# LAN_HUB_imp.net
KiCad netlist of a schematic drawn in EAGLE
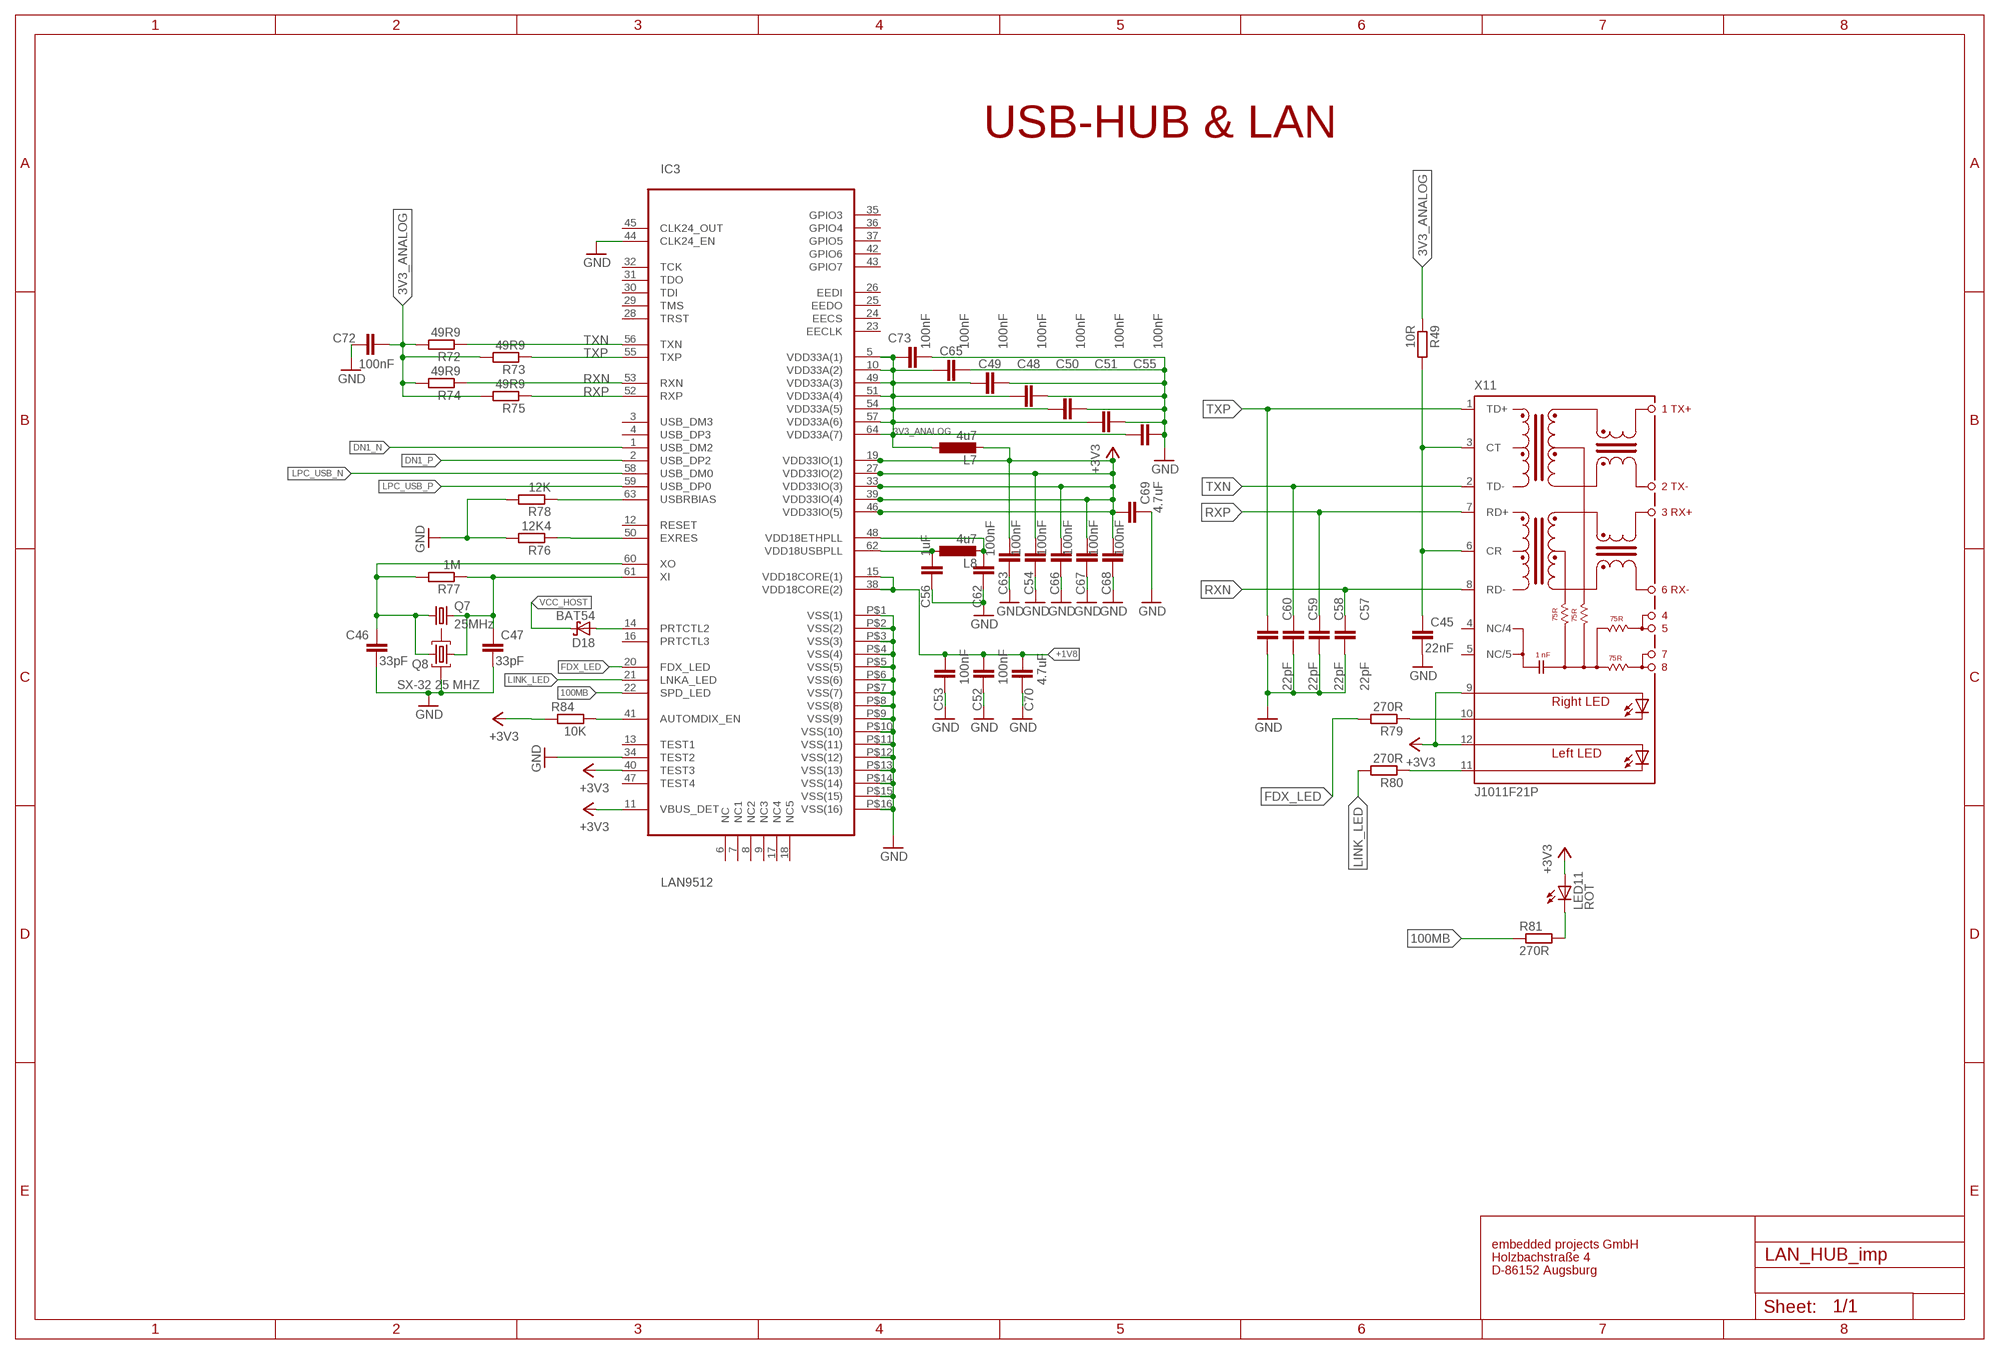
[diagram p0: schematic, sheet 1]

(export (version "E")
  (design (tool "Eeschema 10.0.6"))
  (components
    (comp (ref "C45")
      (value "22nF")
      (footprint "eagle-import:C0805")
      (libsource (lib "eagle-import") (part "C-EUC0805"))
    )
    (comp (ref "C46")
      (value "33pF")
      (footprint "eagle-import:C0805")
      (libsource (lib "eagle-import") (part "C-EUC0805"))
    )
    (comp (ref "C47")
      (value "33pF")
      (footprint "eagle-import:C0805")
      (libsource (lib "eagle-import") (part "C-EUC0805"))
    )
    (comp (ref "C48")
      (value "100nF")
      (footprint "eagle-import:C0805")
      (libsource (lib "eagle-import") (part "C-EUC0805"))
    )
    (comp (ref "C49")
      (value "100nF")
      (footprint "eagle-import:C0805")
      (libsource (lib "eagle-import") (part "C-EUC0805"))
    )
    (comp (ref "C50")
      (value "100nF")
      (footprint "eagle-import:C0805")
      (libsource (lib "eagle-import") (part "C-EUC0805"))
    )
    (comp (ref "C51")
      (value "100nF")
      (footprint "eagle-import:C0805")
      (libsource (lib "eagle-import") (part "C-EUC0805"))
    )
    (comp (ref "C52")
      (value "100nF")
      (footprint "eagle-import:C0805")
      (libsource (lib "eagle-import") (part "C-EUC0805"))
    )
    (comp (ref "C53")
      (value "100nF")
      (footprint "eagle-import:C0805")
      (libsource (lib "eagle-import") (part "C-EUC0805"))
    )
    (comp (ref "C54")
      (value "100nF")
      (footprint "eagle-import:C0805")
      (libsource (lib "eagle-import") (part "C-EUC0805"))
    )
    (comp (ref "C55")
      (value "100nF")
      (footprint "eagle-import:C0805")
      (libsource (lib "eagle-import") (part "C-EUC0805"))
    )
    (comp (ref "C56")
      (value "1uF")
      (footprint "eagle-import:C0805")
      (libsource (lib "eagle-import") (part "C-EUC0805"))
    )
    (comp (ref "C57")
      (value "22pF")
      (footprint "eagle-import:C0805")
      (libsource (lib "eagle-import") (part "C-EUC0805"))
    )
    (comp (ref "C58")
      (value "22pF")
      (footprint "eagle-import:C0805")
      (libsource (lib "eagle-import") (part "C-EUC0805"))
    )
    (comp (ref "C59")
      (value "22pF")
      (footprint "eagle-import:C0805")
      (libsource (lib "eagle-import") (part "C-EUC0805"))
    )
    (comp (ref "C60")
      (value "22pF")
      (footprint "eagle-import:C0805")
      (libsource (lib "eagle-import") (part "C-EUC0805"))
    )
    (comp (ref "C62")
      (value "100nF")
      (footprint "eagle-import:C0805")
      (libsource (lib "eagle-import") (part "C-EUC0805"))
    )
    (comp (ref "C63")
      (value "100nF")
      (footprint "eagle-import:C0805")
      (libsource (lib "eagle-import") (part "C-EUC0805"))
    )
    (comp (ref "C65")
      (value "100nF")
      (footprint "eagle-import:C0805")
      (libsource (lib "eagle-import") (part "C-EUC0805"))
    )
    (comp (ref "C66")
      (value "100nF")
      (footprint "eagle-import:C0805")
      (libsource (lib "eagle-import") (part "C-EUC0805"))
    )
    (comp (ref "C67")
      (value "100nF")
      (footprint "eagle-import:C0805")
      (libsource (lib "eagle-import") (part "C-EUC0805"))
    )
    (comp (ref "C68")
      (value "100nF")
      (footprint "eagle-import:C0805")
      (libsource (lib "eagle-import") (part "C-EUC0805"))
    )
    (comp (ref "C69")
      (value "4.7uF")
      (footprint "eagle-import:C0805")
      (libsource (lib "eagle-import") (part "C-EUC0805"))
    )
    (comp (ref "C70")
      (value "4.7uF")
      (footprint "eagle-import:C0805")
      (libsource (lib "eagle-import") (part "C-EUC0805"))
    )
    (comp (ref "C72")
      (value "100nF")
      (footprint "eagle-import:C0805")
      (libsource (lib "eagle-import") (part "C-EUC0805"))
    )
    (comp (ref "C73")
      (value "100nF")
      (footprint "eagle-import:C0805")
      (libsource (lib "eagle-import") (part "C-EUC0805"))
    )
    (comp (ref "D18")
      (value "BAT54")
      (footprint "eagle-import:SOT-23")
      (libsource (lib "eagle-import") (part "DIODE_BAT54"))
    )
    (comp (ref "IC3")
      (value "LAN9512")
      (footprint "eagle-import:QFN-64")
      (libsource (lib "eagle-import") (part "LAN9512"))
    )
    (comp (ref "L7")
      (value "4u7")
      (footprint "eagle-import:PSU3014")
      (libsource (lib "eagle-import") (part "PSU3014"))
    )
    (comp (ref "L8")
      (value "4u7")
      (footprint "eagle-import:PSU3014")
      (libsource (lib "eagle-import") (part "PSU3014"))
    )
    (comp (ref "LED11")
      (value "ROT")
      (footprint "eagle-import:LED_CHIP-LED0805")
      (libsource (lib "eagle-import") (part "LED_LEDCHIPLED_0805"))
    )
    (comp (ref "Q7")
      (value "25MHz")
      (footprint "eagle-import:HC49UP")
      (libsource (lib "eagle-import") (part "CRYSTALHC49UP"))
    )
    (comp (ref "Q8")
      (value "SX-32 25 MHZ")
      (footprint "eagle-import:SX-32")
      (libsource (lib "eagle-import") (part "SX-32"))
    )
    (comp (ref "R49")
      (value "10R")
      (footprint "eagle-import:R0805")
      (libsource (lib "eagle-import") (part "R-EU_R0805"))
    )
    (comp (ref "R72")
      (value "49R9")
      (footprint "eagle-import:R0805")
      (libsource (lib "eagle-import") (part "R-EU_R0805"))
    )
    (comp (ref "R73")
      (value "49R9")
      (footprint "eagle-import:R0805")
      (libsource (lib "eagle-import") (part "R-EU_R0805"))
    )
    (comp (ref "R74")
      (value "49R9")
      (footprint "eagle-import:R0805")
      (libsource (lib "eagle-import") (part "R-EU_R0805"))
    )
    (comp (ref "R75")
      (value "49R9")
      (footprint "eagle-import:R0805")
      (libsource (lib "eagle-import") (part "R-EU_R0805"))
    )
    (comp (ref "R76")
      (value "12K4")
      (footprint "eagle-import:R0805")
      (libsource (lib "eagle-import") (part "R-EU_R0805"))
    )
    (comp (ref "R77")
      (value "1M")
      (footprint "eagle-import:R0805")
      (libsource (lib "eagle-import") (part "R-EU_R0805"))
    )
    (comp (ref "R78")
      (value "12K")
      (footprint "eagle-import:R0805")
      (libsource (lib "eagle-import") (part "R-EU_R0805"))
    )
    (comp (ref "R79")
      (value "270R")
      (footprint "eagle-import:R0805")
      (libsource (lib "eagle-import") (part "R-EU_R0805"))
    )
    (comp (ref "R80")
      (value "270R")
      (footprint "eagle-import:R0805")
      (libsource (lib "eagle-import") (part "R-EU_R0805"))
    )
    (comp (ref "R81")
      (value "270R")
      (footprint "eagle-import:R0805")
      (libsource (lib "eagle-import") (part "R-EU_R0805"))
    )
    (comp (ref "R84")
      (value "10K")
      (footprint "eagle-import:R0805")
      (libsource (lib "eagle-import") (part "R-EU_R0805"))
    )
    (comp (ref "X11")
      (value "J1011F21P")
      (footprint "eagle-import:J1")
      (libsource (lib "eagle-import") (part "J1011F21P"))
    )
  )
  (nets
    (net (code "1") (name "+1V8") (class "Default")
      (node (ref "C52") (pin "2") (pinfunction "2_2") (pintype "passive"))
      (node (ref "C53") (pin "2") (pinfunction "2_2") (pintype "passive"))
      (node (ref "C70") (pin "1") (pinfunction "1_1") (pintype "passive"))
      (node (ref "IC3") (pin "15") (pinfunction "VDD18CORE(1)_15") (pintype "power_in"))
      (node (ref "IC3") (pin "38") (pinfunction "VDD18CORE(2)_38") (pintype "power_in"))
    )
    (net (code "2") (name "+3V3") (class "Default")
      (node (ref "C54") (pin "2") (pinfunction "2_2") (pintype "passive"))
      (node (ref "C63") (pin "2") (pinfunction "2_2") (pintype "passive"))
      (node (ref "C66") (pin "2") (pinfunction "2_2") (pintype "passive"))
      (node (ref "C67") (pin "2") (pinfunction "2_2") (pintype "passive"))
      (node (ref "C68") (pin "2") (pinfunction "2_2") (pintype "passive"))
      (node (ref "C69") (pin "2") (pinfunction "2_2") (pintype "passive"))
      (node (ref "IC3") (pin "11") (pinfunction "VBUS_DET_11") (pintype "input"))
      (node (ref "IC3") (pin "19") (pinfunction "VDD33IO(1)_19") (pintype "power_in"))
      (node (ref "IC3") (pin "27") (pinfunction "VDD33IO(2)_27") (pintype "power_in"))
      (node (ref "IC3") (pin "33") (pinfunction "VDD33IO(3)_33") (pintype "power_in"))
      (node (ref "IC3") (pin "39") (pinfunction "VDD33IO(4)_39") (pintype "bidirectional"))
      (node (ref "IC3") (pin "40") (pinfunction "TEST3_40") (pintype "bidirectional"))
      (node (ref "IC3") (pin "46") (pinfunction "VDD33IO(5)_46") (pintype "bidirectional"))
      (node (ref "L7") (pin "1") (pinfunction "1_1") (pintype "passive"))
      (node (ref "LED11") (pin "A") (pinfunction "A_A") (pintype "passive"))
      (node (ref "R84") (pin "1") (pinfunction "1_1") (pintype "passive"))
      (node (ref "X11") (pin "12") (pinfunction "AL_12") (pintype "passive"))
      (node (ref "X11") (pin "9") (pinfunction "A-R_9") (pintype "passive"))
    )
    (net (code "3") (name "3V3_ANALOG") (class "Default")
      (node (ref "C48") (pin "2") (pinfunction "2_2") (pintype "passive"))
      (node (ref "C49") (pin "2") (pinfunction "2_2") (pintype "passive"))
      (node (ref "C50") (pin "2") (pinfunction "2_2") (pintype "passive"))
      (node (ref "C51") (pin "2") (pinfunction "2_2") (pintype "passive"))
      (node (ref "C55") (pin "2") (pinfunction "2_2") (pintype "passive"))
      (node (ref "C65") (pin "2") (pinfunction "2_2") (pintype "passive"))
      (node (ref "C72") (pin "1") (pinfunction "1_1") (pintype "passive"))
      (node (ref "C73") (pin "2") (pinfunction "2_2") (pintype "passive"))
      (node (ref "IC3") (pin "10") (pinfunction "VDD33A(2)_10") (pintype "power_in"))
      (node (ref "IC3") (pin "49") (pinfunction "VDD33A(3)_49") (pintype "power_in"))
      (node (ref "IC3") (pin "5") (pinfunction "VDD33A(1)_5") (pintype "power_in"))
      (node (ref "IC3") (pin "51") (pinfunction "VDD33A(4)_51") (pintype "power_in"))
      (node (ref "IC3") (pin "54") (pinfunction "VDD33A(5)_54") (pintype "power_in"))
      (node (ref "IC3") (pin "57") (pinfunction "VDD33A(6)_57") (pintype "power_in"))
      (node (ref "IC3") (pin "64") (pinfunction "VDD33A(7)_64") (pintype "power_in"))
      (node (ref "L7") (pin "2") (pinfunction "2_2") (pintype "passive"))
      (node (ref "R49") (pin "1") (pinfunction "1_1") (pintype "passive"))
      (node (ref "R72") (pin "2") (pinfunction "2_2") (pintype "passive"))
      (node (ref "R73") (pin "2") (pinfunction "2_2") (pintype "passive"))
      (node (ref "R74") (pin "2") (pinfunction "2_2") (pintype "passive"))
      (node (ref "R75") (pin "2") (pinfunction "2_2") (pintype "passive"))
    )
    (net (code "4") (name "100MB") (class "Default")
      (node (ref "IC3") (pin "22") (pinfunction "SPD_LED_22") (pintype "bidirectional"))
      (node (ref "R81") (pin "1") (pinfunction "1_1") (pintype "passive"))
    )
    (net (code "5") (name "DN1_N") (class "Default")
      (node (ref "IC3") (pin "1") (pinfunction "USB_DM2_1") (pintype "bidirectional"))
    )
    (net (code "6") (name "DN1_P") (class "Default")
      (node (ref "IC3") (pin "2") (pinfunction "USB_DP2_2") (pintype "bidirectional"))
    )
    (net (code "7") (name "FDX_LED") (class "Default")
      (node (ref "IC3") (pin "20") (pinfunction "FDX_LED_20") (pintype "bidirectional"))
      (node (ref "R79") (pin "2") (pinfunction "2_2") (pintype "passive"))
    )
    (net (code "8") (name "GND") (class "Default")
      (node (ref "C45") (pin "1") (pinfunction "1_1") (pintype "passive"))
      (node (ref "C46") (pin "1") (pinfunction "1_1") (pintype "passive"))
      (node (ref "C47") (pin "1") (pinfunction "1_1") (pintype "passive"))
      (node (ref "C48") (pin "1") (pinfunction "1_1") (pintype "passive"))
      (node (ref "C49") (pin "1") (pinfunction "1_1") (pintype "passive"))
      (node (ref "C50") (pin "1") (pinfunction "1_1") (pintype "passive"))
      (node (ref "C51") (pin "1") (pinfunction "1_1") (pintype "passive"))
      (node (ref "C52") (pin "1") (pinfunction "1_1") (pintype "passive"))
      (node (ref "C53") (pin "1") (pinfunction "1_1") (pintype "passive"))
      (node (ref "C54") (pin "1") (pinfunction "1_1") (pintype "passive"))
      (node (ref "C55") (pin "1") (pinfunction "1_1") (pintype "passive"))
      (node (ref "C56") (pin "2") (pinfunction "2_2") (pintype "passive"))
      (node (ref "C57") (pin "1") (pinfunction "1_1") (pintype "passive"))
      (node (ref "C58") (pin "1") (pinfunction "1_1") (pintype "passive"))
      (node (ref "C59") (pin "1") (pinfunction "1_1") (pintype "passive"))
      (node (ref "C60") (pin "1") (pinfunction "1_1") (pintype "passive"))
      (node (ref "C62") (pin "2") (pinfunction "2_2") (pintype "passive"))
      (node (ref "C63") (pin "1") (pinfunction "1_1") (pintype "passive"))
      (node (ref "C65") (pin "1") (pinfunction "1_1") (pintype "passive"))
      (node (ref "C66") (pin "1") (pinfunction "1_1") (pintype "passive"))
      (node (ref "C67") (pin "1") (pinfunction "1_1") (pintype "passive"))
      (node (ref "C68") (pin "1") (pinfunction "1_1") (pintype "passive"))
      (node (ref "C69") (pin "1") (pinfunction "1_1") (pintype "passive"))
      (node (ref "C70") (pin "2") (pinfunction "2_2") (pintype "passive"))
      (node (ref "C72") (pin "2") (pinfunction "2_2") (pintype "passive"))
      (node (ref "C73") (pin "1") (pinfunction "1_1") (pintype "passive"))
      (node (ref "IC3") (pin "34") (pinfunction "TEST2_34") (pintype "bidirectional"))
      (node (ref "IC3") (pin "44") (pinfunction "CLK24_EN_44") (pintype "input"))
      (node (ref "IC3") (pin "P$1") (pinfunction "VSS(1)_P$1") (pintype "power_in"))
      (node (ref "IC3") (pin "P$10") (pinfunction "VSS(10)_P$10") (pintype "power_in"))
      (node (ref "IC3") (pin "P$11") (pinfunction "VSS(11)_P$11") (pintype "power_in"))
      (node (ref "IC3") (pin "P$12") (pinfunction "VSS(12)_P$12") (pintype "power_in"))
      (node (ref "IC3") (pin "P$13") (pinfunction "VSS(13)_P$13") (pintype "power_in"))
      (node (ref "IC3") (pin "P$14") (pinfunction "VSS(14)_P$14") (pintype "power_in"))
      (node (ref "IC3") (pin "P$15") (pinfunction "VSS(15)_P$15") (pintype "power_in"))
      (node (ref "IC3") (pin "P$16") (pinfunction "VSS(16)_P$16") (pintype "power_in"))
      (node (ref "IC3") (pin "P$2") (pinfunction "VSS(2)_P$2") (pintype "power_in"))
      (node (ref "IC3") (pin "P$3") (pinfunction "VSS(3)_P$3") (pintype "power_in"))
      (node (ref "IC3") (pin "P$4") (pinfunction "VSS(4)_P$4") (pintype "power_in"))
      (node (ref "IC3") (pin "P$5") (pinfunction "VSS(5)_P$5") (pintype "power_in"))
      (node (ref "IC3") (pin "P$6") (pinfunction "VSS(6)_P$6") (pintype "power_in"))
      (node (ref "IC3") (pin "P$7") (pinfunction "VSS(7)_P$7") (pintype "power_in"))
      (node (ref "IC3") (pin "P$8") (pinfunction "VSS(8)_P$8") (pintype "power_in"))
      (node (ref "IC3") (pin "P$9") (pinfunction "VSS(9)_P$9") (pintype "power_in"))
      (node (ref "Q8") (pin "2") (pinfunction "3_2") (pintype "passive"))
      (node (ref "R76") (pin "2") (pinfunction "2_2") (pintype "passive"))
      (node (ref "R78") (pin "2") (pinfunction "2_2") (pintype "passive"))
    )
    (net (code "9") (name "LINK_LED") (class "Default")
      (node (ref "IC3") (pin "21") (pinfunction "LNKA_LED_21") (pintype "bidirectional"))
      (node (ref "R80") (pin "2") (pinfunction "2_2") (pintype "passive"))
    )
    (net (code "10") (name "LPC_USB_N") (class "Default")
      (node (ref "IC3") (pin "58") (pinfunction "USB_DM0_58") (pintype "bidirectional"))
    )
    (net (code "11") (name "LPC_USB_P") (class "Default")
      (node (ref "IC3") (pin "59") (pinfunction "USB_DP0_59") (pintype "bidirectional"))
    )
    (net (code "12") (name "Net-(D18-A)") (class "Default")
      (node (ref "D18") (pin "1") (pinfunction "A_1") (pintype "passive"))
      (node (ref "IC3") (pin "14") (pinfunction "PRTCTL2_14") (pintype "bidirectional"))
    )
    (net (code "13") (name "Net-(IC3-AUTOMDIX_EN)") (class "Default")
      (node (ref "IC3") (pin "41") (pinfunction "AUTOMDIX_EN_41") (pintype "bidirectional"))
      (node (ref "R84") (pin "2") (pinfunction "2_2") (pintype "passive"))
    )
    (net (code "14") (name "Net-(IC3-EXRES)") (class "Default")
      (node (ref "IC3") (pin "50") (pinfunction "EXRES_50") (pintype "input"))
      (node (ref "R76") (pin "1") (pinfunction "1_1") (pintype "passive"))
    )
    (net (code "15") (name "Net-(IC3-USBRBIAS)") (class "Default")
      (node (ref "IC3") (pin "63") (pinfunction "USBRBIAS_63") (pintype "input"))
      (node (ref "R78") (pin "1") (pinfunction "1_1") (pintype "passive"))
    )
    (net (code "16") (name "Net-(IC3-VDD18ETHPLL)") (class "Default")
      (node (ref "C62") (pin "1") (pinfunction "1_1") (pintype "passive"))
      (node (ref "IC3") (pin "48") (pinfunction "VDD18ETHPLL_48") (pintype "power_in"))
      (node (ref "L8") (pin "1") (pinfunction "1_1") (pintype "passive"))
    )
    (net (code "17") (name "Net-(IC3-VDD18USBPLL)") (class "Default")
      (node (ref "C56") (pin "1") (pinfunction "1_1") (pintype "passive"))
      (node (ref "IC3") (pin "62") (pinfunction "VDD18USBPLL_62") (pintype "bidirectional"))
      (node (ref "L8") (pin "2") (pinfunction "2_2") (pintype "passive"))
    )
    (net (code "18") (name "Net-(IC3-XI)") (class "Default")
      (node (ref "C47") (pin "2") (pinfunction "2_2") (pintype "passive"))
      (node (ref "IC3") (pin "61") (pinfunction "XI_61") (pintype "input"))
      (node (ref "Q7") (pin "2") (pinfunction "2_2") (pintype "passive"))
      (node (ref "Q8") (pin "1") (pinfunction "1_1") (pintype "passive"))
      (node (ref "R77") (pin "1") (pinfunction "1_1") (pintype "passive"))
    )
    (net (code "19") (name "Net-(IC3-XO)") (class "Default")
      (node (ref "C46") (pin "2") (pinfunction "2_2") (pintype "passive"))
      (node (ref "IC3") (pin "60") (pinfunction "XO_60") (pintype "output"))
      (node (ref "Q7") (pin "1") (pinfunction "1_1") (pintype "passive"))
      (node (ref "Q8") (pin "3") (pinfunction "2_3") (pintype "passive"))
      (node (ref "R77") (pin "2") (pinfunction "2_2") (pintype "passive"))
    )
    (net (code "20") (name "Net-(LED11-PadC)") (class "Default")
      (node (ref "LED11") (pin "C") (pinfunction "C_C") (pintype "passive"))
      (node (ref "R81") (pin "2") (pinfunction "2_2") (pintype "passive"))
    )
    (net (code "21") (name "Net-(X11-C-L)") (class "Default")
      (node (ref "R80") (pin "1") (pinfunction "1_1") (pintype "passive"))
      (node (ref "X11") (pin "11") (pinfunction "C-L_11") (pintype "passive"))
    )
    (net (code "22") (name "Net-(X11-C-R)") (class "Default")
      (node (ref "R79") (pin "1") (pinfunction "1_1") (pintype "passive"))
      (node (ref "X11") (pin "10") (pinfunction "C-R_10") (pintype "passive"))
    )
    (net (code "23") (name "Net-(X11-CR)") (class "Default")
      (node (ref "C45") (pin "2") (pinfunction "2_2") (pintype "passive"))
      (node (ref "R49") (pin "2") (pinfunction "2_2") (pintype "passive"))
      (node (ref "X11") (pin "3") (pinfunction "CT_3") (pintype "input"))
      (node (ref "X11") (pin "6") (pinfunction "CR_6") (pintype "input"))
    )
    (net (code "24") (name "RXN") (class "Default")
      (node (ref "C57") (pin "2") (pinfunction "2_2") (pintype "passive"))
      (node (ref "IC3") (pin "53") (pinfunction "RXN_53") (pintype "bidirectional"))
      (node (ref "R74") (pin "1") (pinfunction "1_1") (pintype "passive"))
      (node (ref "X11") (pin "8") (pinfunction "RD-_8") (pintype "input"))
    )
    (net (code "25") (name "RXP") (class "Default")
      (node (ref "C58") (pin "2") (pinfunction "2_2") (pintype "passive"))
      (node (ref "IC3") (pin "52") (pinfunction "RXP_52") (pintype "bidirectional"))
      (node (ref "R75") (pin "1") (pinfunction "1_1") (pintype "passive"))
      (node (ref "X11") (pin "7") (pinfunction "RD+_7") (pintype "input"))
    )
    (net (code "26") (name "TXN") (class "Default")
      (node (ref "C59") (pin "2") (pinfunction "2_2") (pintype "passive"))
      (node (ref "IC3") (pin "56") (pinfunction "TXN_56") (pintype "bidirectional"))
      (node (ref "R72") (pin "1") (pinfunction "1_1") (pintype "passive"))
      (node (ref "X11") (pin "2") (pinfunction "TD-_2") (pintype "input"))
    )
    (net (code "27") (name "TXP") (class "Default")
      (node (ref "C60") (pin "2") (pinfunction "2_2") (pintype "passive"))
      (node (ref "IC3") (pin "55") (pinfunction "TXP_55") (pintype "bidirectional"))
      (node (ref "R73") (pin "1") (pinfunction "1_1") (pintype "passive"))
      (node (ref "X11") (pin "1") (pinfunction "TD+_1") (pintype "input"))
    )
    (net (code "28") (name "VCC_HOST") (class "Default")
      (node (ref "D18") (pin "3") (pinfunction "C_3") (pintype "passive"))
    )
    (net (code "29") (name "unconnected-(IC3-CLK24_OUT-Pad45)") (class "Default")
      (node (ref "IC3") (pin "45") (pinfunction "CLK24_OUT_45") (pintype "bidirectional"))
    )
    (net (code "30") (name "unconnected-(IC3-EECLK-Pad23)") (class "Default")
      (node (ref "IC3") (pin "23") (pinfunction "EECLK_23") (pintype "bidirectional"))
    )
    (net (code "31") (name "unconnected-(IC3-EECS-Pad24)") (class "Default")
      (node (ref "IC3") (pin "24") (pinfunction "EECS_24") (pintype "output"))
    )
    (net (code "32") (name "unconnected-(IC3-EEDI-Pad26)") (class "Default")
      (node (ref "IC3") (pin "26") (pinfunction "EEDI_26") (pintype "input"))
    )
    (net (code "33") (name "unconnected-(IC3-EEDO-Pad25)") (class "Default")
      (node (ref "IC3") (pin "25") (pinfunction "EEDO_25") (pintype "output"))
    )
    (net (code "34") (name "unconnected-(IC3-GPIO3-Pad35)") (class "Default")
      (node (ref "IC3") (pin "35") (pinfunction "GPIO3_35") (pintype "bidirectional"))
    )
    (net (code "35") (name "unconnected-(IC3-GPIO4-Pad36)") (class "Default")
      (node (ref "IC3") (pin "36") (pinfunction "GPIO4_36") (pintype "bidirectional"))
    )
    (net (code "36") (name "unconnected-(IC3-GPIO5-Pad37)") (class "Default")
      (node (ref "IC3") (pin "37") (pinfunction "GPIO5_37") (pintype "bidirectional"))
    )
    (net (code "37") (name "unconnected-(IC3-GPIO6-Pad42)") (class "Default")
      (node (ref "IC3") (pin "42") (pinfunction "GPIO6_42") (pintype "bidirectional"))
    )
    (net (code "38") (name "unconnected-(IC3-GPIO7-Pad43)") (class "Default")
      (node (ref "IC3") (pin "43") (pinfunction "GPIO7_43") (pintype "bidirectional"))
    )
    (net (code "39") (name "unconnected-(IC3-NC-Pad6)") (class "Default")
      (node (ref "IC3") (pin "6") (pinfunction "NC_6") (pintype "no_connect"))
    )
    (net (code "40") (name "unconnected-(IC3-NC1-Pad7)") (class "Default")
      (node (ref "IC3") (pin "7") (pinfunction "NC1_7") (pintype "no_connect"))
    )
    (net (code "41") (name "unconnected-(IC3-NC2-Pad8)") (class "Default")
      (node (ref "IC3") (pin "8") (pinfunction "NC2_8") (pintype "no_connect"))
    )
    (net (code "42") (name "unconnected-(IC3-NC3-Pad9)") (class "Default")
      (node (ref "IC3") (pin "9") (pinfunction "NC3_9") (pintype "no_connect"))
    )
    (net (code "43") (name "unconnected-(IC3-NC4-Pad17)") (class "Default")
      (node (ref "IC3") (pin "17") (pinfunction "NC4_17") (pintype "no_connect"))
    )
    (net (code "44") (name "unconnected-(IC3-NC5-Pad18)") (class "Default")
      (node (ref "IC3") (pin "18") (pinfunction "NC5_18") (pintype "no_connect"))
    )
    (net (code "45") (name "unconnected-(IC3-PRTCTL3-Pad16)") (class "Default")
      (node (ref "IC3") (pin "16") (pinfunction "PRTCTL3_16") (pintype "bidirectional"))
    )
    (net (code "46") (name "unconnected-(IC3-RESET-Pad12)") (class "Default")
      (node (ref "IC3") (pin "12") (pinfunction "RESET_12") (pintype "input"))
    )
    (net (code "47") (name "unconnected-(IC3-TCK-Pad32)") (class "Default")
      (node (ref "IC3") (pin "32") (pinfunction "TCK_32") (pintype "output"))
    )
    (net (code "48") (name "unconnected-(IC3-TDI-Pad30)") (class "Default")
      (node (ref "IC3") (pin "30") (pinfunction "TDI_30") (pintype "input"))
    )
    (net (code "49") (name "unconnected-(IC3-TDO-Pad31)") (class "Default")
      (node (ref "IC3") (pin "31") (pinfunction "TDO_31") (pintype "bidirectional"))
    )
    (net (code "50") (name "unconnected-(IC3-TEST1-Pad13)") (class "Default")
      (node (ref "IC3") (pin "13") (pinfunction "TEST1_13") (pintype "bidirectional"))
    )
    (net (code "51") (name "unconnected-(IC3-TEST4-Pad47)") (class "Default")
      (node (ref "IC3") (pin "47") (pinfunction "TEST4_47") (pintype "bidirectional"))
    )
    (net (code "52") (name "unconnected-(IC3-TMS-Pad29)") (class "Default")
      (node (ref "IC3") (pin "29") (pinfunction "TMS_29") (pintype "input"))
    )
    (net (code "53") (name "unconnected-(IC3-TRST-Pad28)") (class "Default")
      (node (ref "IC3") (pin "28") (pinfunction "TRST_28") (pintype "input"))
    )
    (net (code "54") (name "unconnected-(IC3-USB_DM3-Pad3)") (class "Default")
      (node (ref "IC3") (pin "3") (pinfunction "USB_DM3_3") (pintype "bidirectional"))
    )
    (net (code "55") (name "unconnected-(IC3-USB_DP3-Pad4)") (class "Default")
      (node (ref "IC3") (pin "4") (pinfunction "USB_DP3_4") (pintype "bidirectional"))
    )
    (net (code "56") (name "unconnected-(Q8-Pad4)") (class "Default")
      (node (ref "Q8") (pin "4") (pinfunction "4_4") (pintype "passive"))
    )
    (net (code "57") (name "unconnected-(X11-NC{slash}4-Pad4)") (class "Default")
      (node (ref "X11") (pin "4") (pinfunction "NC/4_4") (pintype "input"))
    )
    (net (code "58") (name "unconnected-(X11-NC{slash}5-Pad5)") (class "Default")
      (node (ref "X11") (pin "5") (pinfunction "NC/5_5") (pintype "input"))
    )
  )
)
